# interface.net
KiCad netlist of a schematic drawn in Altium Designer
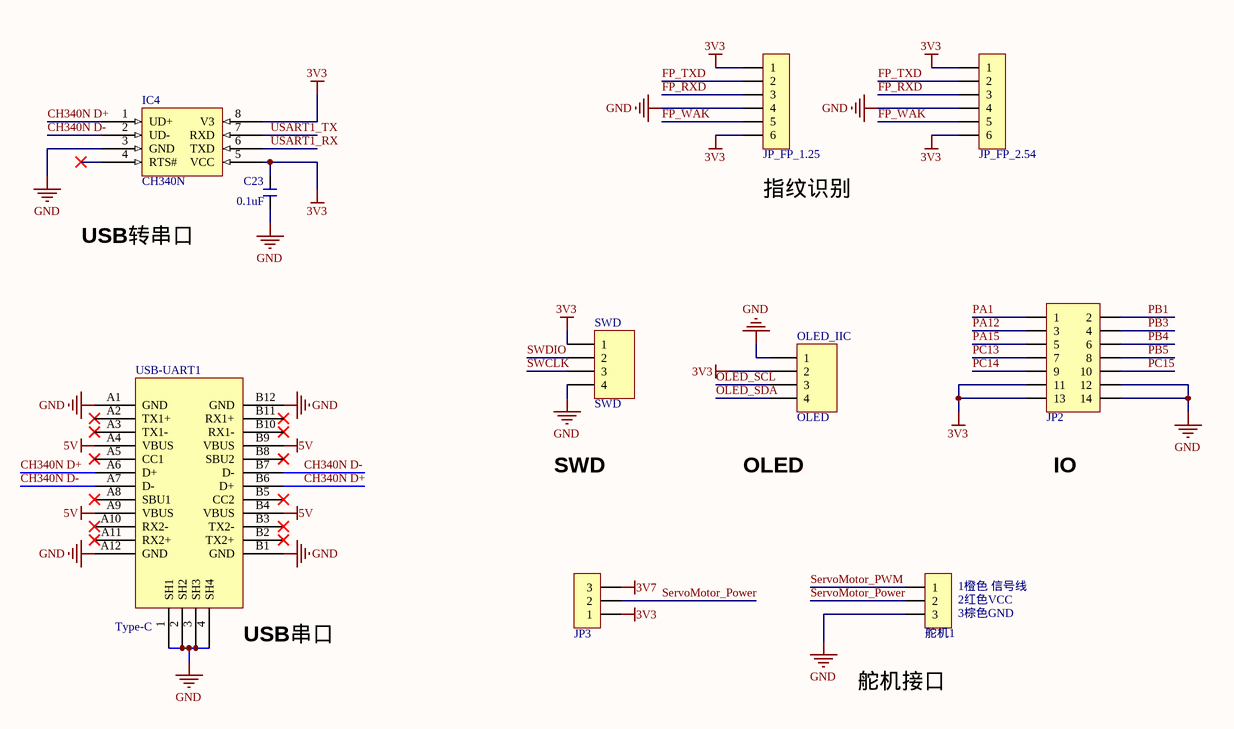
[diagram p0: interface.SchDoc]

(export (version "E")
  (design (tool "Eeschema 10.0.6"))
  (components
    (comp (ref "C23")
      (value "0.1uF")
      (footprint "C 0603_M")
      (description "无极性贴片电容")
      (fields (field (name "版权归属") "源创客"))
      (libsource (lib "altium-import") (part "root_1_C_"))
    )
    (comp (ref "IC4")
      (value "CH340N")
      (footprint "SOP8_N")
      (description "USB 转串口芯片 CH330/CH340N")
      (libsource (lib "altium-import") (part "root_0_CH340N_"))
    )
    (comp (ref "JP2")
      (value "Header 2X7")
      (footprint "HDR2.54-LI-2x7P")
      (description "7*2P接插件")
      (fields (field (name "版权归属") "源创客"))
      (libsource (lib "4.5   - 接插件-脚距2.54") (part "Header 7X2"))
    )
    (comp (ref "JP3")
      (value "HDR-1X3")
      (footprint "HDR2.54-LI-3P")
      (description "3P接插件")
      (fields (field (name "版权归属") "源创客"))
      (libsource (lib "4.5   - 接插件-脚距2.54") (part "Header 3"))
    )
    (comp (ref "JP_FP_1.25")
      (value "HDR-1X6")
      (footprint "MX 1.25-WS-6P")
      (description "6P接插件")
      (fields (field (name "版权归属") "源创客"))
      (libsource (lib "4.2   - 接插件-脚距1.25") (part "Header 6"))
    )
    (comp (ref "JP_FP_2.54")
      (value "HDR-1X6")
      (footprint "HDR2.54-LI-2x3P")
      (description "6P接插件")
      (fields (field (name "版权归属") "源创客"))
      (libsource (lib "4.5   - 接插件-脚距2.54") (part "Header 6"))
    )
    (comp (ref "OLED_IIC")
      (value "OLED")
      (footprint "HDR2.54-LI-4P")
      (description "Header, 4-Pin")
      (fields (field (name "PUBLISHER") "Altium Limited"))
      (libsource (lib "Miscellaneous Connectors") (part "Header 4"))
    )
    (comp (ref "SWD")
      (value "SWD")
      (footprint "HDR2.54-LI-4P")
      (description "Header, 4-Pin")
      (fields (field (name "PUBLISHER") "Altium Limited"))
      (libsource (lib "Miscellaneous Connectors") (part "Header 4"))
    )
    (comp (ref "USB-UART1")
      (value "Type-C")
      (footprint "TYPE-C")
      (libsource (lib "altium-import") (part "root_0_Type-C_"))
    )
    (comp (ref "舵机1")
      (value "HDR-1X3")
      (footprint "HDR2.54-LI-3P")
      (description "3P接插件")
      (fields (field (name "版权归属") "源创客"))
      (libsource (lib "") (part "Header 3_1"))
    )
  )
  (nets
    (net (code "1") (name "/CH340N D+") (class "Default")
      (node (ref "IC4") (pin "1") (pinfunction "UD+_1") (pintype "input"))
      (node (ref "USB-UART1") (pin "A6") (pinfunction "D+_A6") (pintype "passive"))
      (node (ref "USB-UART1") (pin "B6") (pinfunction "D+_B6") (pintype "passive"))
    )
    (net (code "2") (name "/CH340N D-") (class "Default")
      (node (ref "IC4") (pin "2") (pinfunction "UD-_2") (pintype "input"))
      (node (ref "USB-UART1") (pin "A7") (pinfunction "D-_A7") (pintype "passive"))
      (node (ref "USB-UART1") (pin "B7") (pinfunction "D-_B7") (pintype "passive"))
    )
    (net (code "3") (name "/FP_RXD") (class "Default")
      (node (ref "JP_FP_1.25") (pin "3") (pinfunction "3_3") (pintype "passive"))
      (node (ref "JP_FP_2.54") (pin "3") (pinfunction "3_3") (pintype "passive"))
    )
    (net (code "4") (name "/FP_TXD") (class "Default")
      (node (ref "JP_FP_1.25") (pin "2") (pinfunction "2_2") (pintype "passive"))
      (node (ref "JP_FP_2.54") (pin "2") (pinfunction "2_2") (pintype "passive"))
    )
    (net (code "5") (name "/FP_WAK") (class "Default")
      (node (ref "JP_FP_1.25") (pin "5") (pinfunction "5_5") (pintype "passive"))
      (node (ref "JP_FP_2.54") (pin "5") (pinfunction "5_5") (pintype "passive"))
    )
    (net (code "6") (name "/OLED_SCL") (class "Default")
      (node (ref "OLED_IIC") (pin "3") (pinfunction "3_3") (pintype "passive"))
    )
    (net (code "7") (name "/OLED_SDA") (class "Default")
      (node (ref "OLED_IIC") (pin "4") (pinfunction "4_4") (pintype "passive"))
    )
    (net (code "8") (name "/PA1") (class "Default")
      (node (ref "JP2") (pin "1") (pinfunction "1_1") (pintype "passive"))
    )
    (net (code "9") (name "/PA12") (class "Default")
      (node (ref "JP2") (pin "3") (pinfunction "3_3") (pintype "passive"))
    )
    (net (code "10") (name "/PA15") (class "Default")
      (node (ref "JP2") (pin "5") (pinfunction "5_5") (pintype "passive"))
    )
    (net (code "11") (name "/PB1") (class "Default")
      (node (ref "JP2") (pin "2") (pinfunction "2_2") (pintype "passive"))
    )
    (net (code "12") (name "/PB3") (class "Default")
      (node (ref "JP2") (pin "4") (pinfunction "4_4") (pintype "passive"))
    )
    (net (code "13") (name "/PB4") (class "Default")
      (node (ref "JP2") (pin "6") (pinfunction "6_6") (pintype "passive"))
    )
    (net (code "14") (name "/PB5") (class "Default")
      (node (ref "JP2") (pin "8") (pinfunction "8_8") (pintype "passive"))
    )
    (net (code "15") (name "/PC13") (class "Default")
      (node (ref "JP2") (pin "7") (pinfunction "7_7") (pintype "passive"))
    )
    (net (code "16") (name "/PC14") (class "Default")
      (node (ref "JP2") (pin "9") (pinfunction "9_9") (pintype "passive"))
    )
    (net (code "17") (name "/PC15") (class "Default")
      (node (ref "JP2") (pin "10") (pinfunction "10_10") (pintype "passive"))
    )
    (net (code "18") (name "/SWCLK") (class "Default")
      (node (ref "SWD") (pin "3") (pinfunction "3_3") (pintype "passive"))
    )
    (net (code "19") (name "/SWDIO") (class "Default")
      (node (ref "SWD") (pin "2") (pinfunction "2_2") (pintype "passive"))
    )
    (net (code "20") (name "/ServoMotor_PWM") (class "Default")
      (node (ref "舵机1") (pin "1") (pinfunction "1_1") (pintype "passive"))
    )
    (net (code "21") (name "/ServoMotor_Power") (class "Default")
      (node (ref "JP3") (pin "2") (pinfunction "2_2") (pintype "passive"))
      (node (ref "舵机1") (pin "2") (pinfunction "2_2") (pintype "passive"))
    )
    (net (code "22") (name "/USART1_RX") (class "Default")
      (node (ref "IC4") (pin "6") (pinfunction "TXD_6") (pintype "input"))
    )
    (net (code "23") (name "/USART1_TX") (class "Default")
      (node (ref "IC4") (pin "7") (pinfunction "RXD_7") (pintype "input"))
    )
    (net (code "24") (name "3V3") (class "Default")
      (node (ref "C23") (pin "2") (pinfunction "2_2") (pintype "passive"))
      (node (ref "IC4") (pin "5") (pinfunction "VCC_5") (pintype "input"))
      (node (ref "IC4") (pin "8") (pinfunction "V3_8") (pintype "input"))
      (node (ref "JP2") (pin "11") (pinfunction "11_11") (pintype "passive"))
      (node (ref "JP2") (pin "13") (pinfunction "13_13") (pintype "passive"))
      (node (ref "JP3") (pin "1") (pinfunction "1_1") (pintype "passive"))
      (node (ref "JP_FP_1.25") (pin "1") (pinfunction "1_1") (pintype "passive"))
      (node (ref "JP_FP_1.25") (pin "6") (pinfunction "6_6") (pintype "passive"))
      (node (ref "JP_FP_2.54") (pin "1") (pinfunction "1_1") (pintype "passive"))
      (node (ref "JP_FP_2.54") (pin "6") (pinfunction "6_6") (pintype "passive"))
      (node (ref "OLED_IIC") (pin "2") (pinfunction "2_2") (pintype "passive"))
      (node (ref "SWD") (pin "1") (pinfunction "1_1") (pintype "passive"))
    )
    (net (code "25") (name "3V7") (class "Default")
      (node (ref "JP3") (pin "3") (pinfunction "3_3") (pintype "passive"))
    )
    (net (code "26") (name "5V") (class "Default")
      (node (ref "USB-UART1") (pin "A4") (pinfunction "VBUS_A4") (pintype "passive"))
      (node (ref "USB-UART1") (pin "A9") (pinfunction "VBUS_A9") (pintype "passive"))
      (node (ref "USB-UART1") (pin "B4") (pinfunction "VBUS_B4") (pintype "passive"))
      (node (ref "USB-UART1") (pin "B9") (pinfunction "VBUS_B9") (pintype "passive"))
    )
    (net (code "27") (name "GND") (class "Default")
      (node (ref "C23") (pin "1") (pinfunction "1_1") (pintype "passive"))
      (node (ref "IC4") (pin "3") (pinfunction "GND_3") (pintype "input"))
      (node (ref "JP2") (pin "12") (pinfunction "12_12") (pintype "passive"))
      (node (ref "JP2") (pin "14") (pinfunction "14_14") (pintype "passive"))
      (node (ref "JP_FP_1.25") (pin "4") (pinfunction "4_4") (pintype "passive"))
      (node (ref "JP_FP_2.54") (pin "4") (pinfunction "4_4") (pintype "passive"))
      (node (ref "OLED_IIC") (pin "1") (pinfunction "1_1") (pintype "passive"))
      (node (ref "SWD") (pin "4") (pinfunction "4_4") (pintype "passive"))
      (node (ref "USB-UART1") (pin "1") (pinfunction "SH1_1") (pintype "passive"))
      (node (ref "USB-UART1") (pin "2") (pinfunction "SH2_2") (pintype "passive"))
      (node (ref "USB-UART1") (pin "3") (pinfunction "SH3_3") (pintype "passive"))
      (node (ref "USB-UART1") (pin "4") (pinfunction "SH4_4") (pintype "passive"))
      (node (ref "USB-UART1") (pin "A1") (pinfunction "GND_A1") (pintype "passive"))
      (node (ref "USB-UART1") (pin "A12") (pinfunction "GND_A12") (pintype "passive"))
      (node (ref "USB-UART1") (pin "B1") (pinfunction "GND_B1") (pintype "passive"))
      (node (ref "USB-UART1") (pin "B12") (pinfunction "GND_B12") (pintype "passive"))
      (node (ref "舵机1") (pin "3") (pinfunction "3_3") (pintype "passive"))
    )
    (net (code "28") (name "unconnected-(IC4-RTS#-Pad4)") (class "Default")
      (node (ref "IC4") (pin "4") (pinfunction "RTS#_4") (pintype "input+no_connect"))
    )
    (net (code "29") (name "unconnected-(USB-UART1-CC1-PadA5)") (class "Default")
      (node (ref "USB-UART1") (pin "A5") (pinfunction "CC1_A5") (pintype "passive+no_connect"))
    )
    (net (code "30") (name "unconnected-(USB-UART1-CC2-PadB5)") (class "Default")
      (node (ref "USB-UART1") (pin "B5") (pinfunction "CC2_B5") (pintype "passive+no_connect"))
    )
    (net (code "31") (name "unconnected-(USB-UART1-RX1+-PadB11)") (class "Default")
      (node (ref "USB-UART1") (pin "B11") (pinfunction "RX1+_B11") (pintype "passive+no_connect"))
    )
    (net (code "32") (name "unconnected-(USB-UART1-RX1--PadB10)") (class "Default")
      (node (ref "USB-UART1") (pin "B10") (pinfunction "RX1-_B10") (pintype "passive+no_connect"))
    )
    (net (code "33") (name "unconnected-(USB-UART1-RX2+-PadA11)") (class "Default")
      (node (ref "USB-UART1") (pin "A11") (pinfunction "RX2+_A11") (pintype "passive+no_connect"))
    )
    (net (code "34") (name "unconnected-(USB-UART1-RX2--PadA10)") (class "Default")
      (node (ref "USB-UART1") (pin "A10") (pinfunction "RX2-_A10") (pintype "passive+no_connect"))
    )
    (net (code "35") (name "unconnected-(USB-UART1-SBU1-PadA8)") (class "Default")
      (node (ref "USB-UART1") (pin "A8") (pinfunction "SBU1_A8") (pintype "passive+no_connect"))
    )
    (net (code "36") (name "unconnected-(USB-UART1-SBU2-PadB8)") (class "Default")
      (node (ref "USB-UART1") (pin "B8") (pinfunction "SBU2_B8") (pintype "passive+no_connect"))
    )
    (net (code "37") (name "unconnected-(USB-UART1-TX1+-PadA2)") (class "Default")
      (node (ref "USB-UART1") (pin "A2") (pinfunction "TX1+_A2") (pintype "passive+no_connect"))
    )
    (net (code "38") (name "unconnected-(USB-UART1-TX1--PadA3)") (class "Default")
      (node (ref "USB-UART1") (pin "A3") (pinfunction "TX1-_A3") (pintype "passive+no_connect"))
    )
    (net (code "39") (name "unconnected-(USB-UART1-TX2+-PadB2)") (class "Default")
      (node (ref "USB-UART1") (pin "B2") (pinfunction "TX2+_B2") (pintype "passive+no_connect"))
    )
    (net (code "40") (name "unconnected-(USB-UART1-TX2--PadB3)") (class "Default")
      (node (ref "USB-UART1") (pin "B3") (pinfunction "TX2-_B3") (pintype "passive+no_connect"))
    )
  )
)
